# turbo_jumper.net
KiCad netlist of a schematic drawn in EAGLE
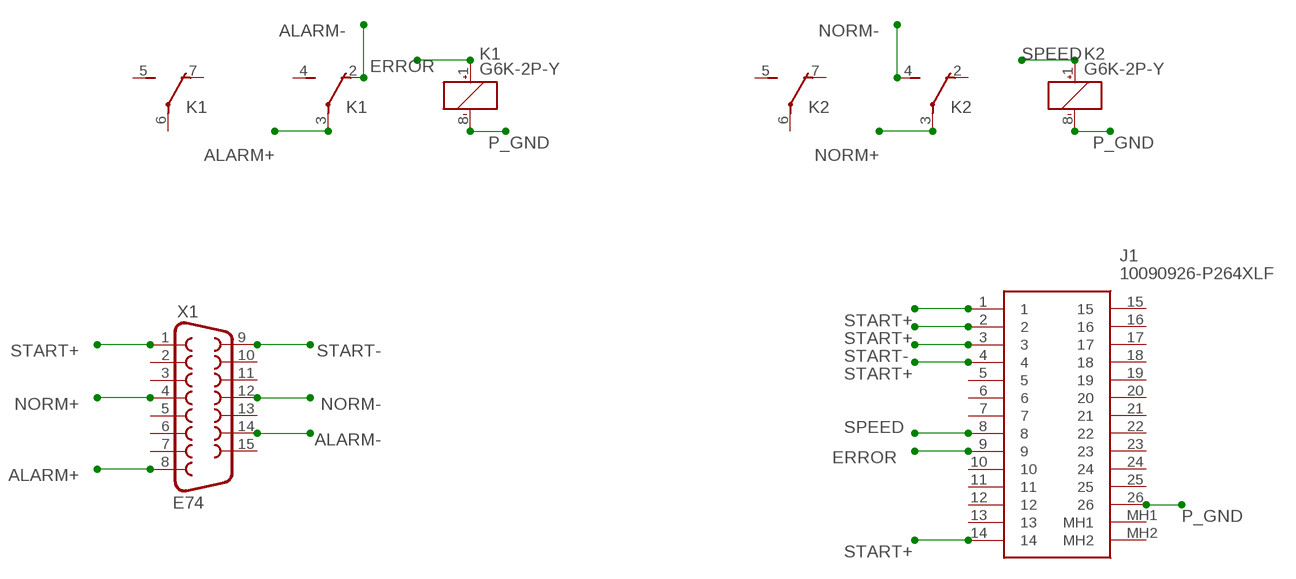
[diagram p0: schematic, sheet 1]

(export (version "E")
  (design (tool "Eeschema 10.0.6"))
  (components
    (comp (ref "J1")
      (value "10090926-P264XLF")
      (footprint "eagle-import:10090926P264XLF")
      (fields (field (name "MOUSER_PART_NUMBER") "649-10090926-P264XLF"))
      (libsource (lib "eagle-import") (part "10090926-P264XLF"))
    )
    (comp (ref "K1")
      (value "G6K-2P-Y")
      (footprint "eagle-import:G6K-2P-Y")
      (fields (field (name "MF") "OMRON COMPONENTS USA") (field (name "MPN") "G6K-2P-Y DC12"))
      (libsource (lib "eagle-import") (part "G6K-2P-Y"))
    )
    (comp (ref "K2")
      (value "G6K-2P-Y")
      (footprint "eagle-import:G6K-2P-Y")
      (fields (field (name "MF") "OMRON COMPONENTS USA") (field (name "MPN") "G6K-2P-Y DC12"))
      (libsource (lib "eagle-import") (part "G6K-2P-Y"))
    )
    (comp (ref "X1")
      (value "E74")
      (footprint "eagle-import:F15VP")
      (libsource (lib "eagle-import") (part "F15VP"))
    )
  )
  (nets
    (net (code "1") (name "/ALARM+") (class "Default")
      (node (ref "K1") (pin "3") (pinfunction "P_3") (pintype "passive"))
      (node (ref "X1") (pin "8") (pinfunction "8_8") (pintype "passive"))
    )
    (net (code "2") (name "/ALARM-") (class "Default")
      (node (ref "K1") (pin "2") (pinfunction "O_2") (pintype "passive"))
      (node (ref "X1") (pin "14") (pinfunction "14_14") (pintype "passive"))
    )
    (net (code "3") (name "/ERROR") (class "Default")
      (node (ref "J1") (pin "9") (pinfunction "9_9") (pintype "bidirectional"))
      (node (ref "K1") (pin "1") (pinfunction "+_1") (pintype "passive"))
    )
    (net (code "4") (name "/NORM+") (class "Default")
      (node (ref "K2") (pin "3") (pinfunction "P_3") (pintype "passive"))
      (node (ref "X1") (pin "4") (pinfunction "4_4") (pintype "passive"))
    )
    (net (code "5") (name "/NORM-") (class "Default")
      (node (ref "K2") (pin "4") (pinfunction "S_4") (pintype "passive"))
      (node (ref "X1") (pin "12") (pinfunction "12_12") (pintype "passive"))
    )
    (net (code "6") (name "/P_GND") (class "Default")
      (node (ref "J1") (pin "26") (pinfunction "26_26") (pintype "bidirectional"))
      (node (ref "K1") (pin "8") (pinfunction "-_8") (pintype "passive"))
      (node (ref "K2") (pin "8") (pinfunction "-_8") (pintype "passive"))
    )
    (net (code "7") (name "/SPEED") (class "Default")
      (node (ref "J1") (pin "8") (pinfunction "8_8") (pintype "bidirectional"))
      (node (ref "K2") (pin "1") (pinfunction "+_1") (pintype "passive"))
    )
    (net (code "8") (name "/START+") (class "Default")
      (node (ref "J1") (pin "1") (pinfunction "1_1") (pintype "bidirectional"))
      (node (ref "J1") (pin "14") (pinfunction "14_14") (pintype "bidirectional"))
      (node (ref "J1") (pin "2") (pinfunction "2_2") (pintype "bidirectional"))
      (node (ref "J1") (pin "4") (pinfunction "4_4") (pintype "bidirectional"))
      (node (ref "X1") (pin "1") (pinfunction "1_1") (pintype "passive"))
    )
    (net (code "9") (name "/START-") (class "Default")
      (node (ref "J1") (pin "3") (pinfunction "3_3") (pintype "bidirectional"))
      (node (ref "X1") (pin "9") (pinfunction "9_9") (pintype "passive"))
    )
    (net (code "10") (name "unconnected-(J1-Pad5)") (class "Default")
      (node (ref "J1") (pin "5") (pinfunction "5_5") (pintype "bidirectional"))
    )
    (net (code "11") (name "unconnected-(J1-Pad6)") (class "Default")
      (node (ref "J1") (pin "6") (pinfunction "6_6") (pintype "bidirectional"))
    )
    (net (code "12") (name "unconnected-(J1-Pad7)") (class "Default")
      (node (ref "J1") (pin "7") (pinfunction "7_7") (pintype "bidirectional"))
    )
    (net (code "13") (name "unconnected-(J1-Pad10)") (class "Default")
      (node (ref "J1") (pin "10") (pinfunction "10_10") (pintype "bidirectional"))
    )
    (net (code "14") (name "unconnected-(J1-Pad11)") (class "Default")
      (node (ref "J1") (pin "11") (pinfunction "11_11") (pintype "bidirectional"))
    )
    (net (code "15") (name "unconnected-(J1-Pad12)") (class "Default")
      (node (ref "J1") (pin "12") (pinfunction "12_12") (pintype "bidirectional"))
    )
    (net (code "16") (name "unconnected-(J1-Pad13)") (class "Default")
      (node (ref "J1") (pin "13") (pinfunction "13_13") (pintype "bidirectional"))
    )
    (net (code "17") (name "unconnected-(J1-Pad15)") (class "Default")
      (node (ref "J1") (pin "15") (pinfunction "15_15") (pintype "bidirectional"))
    )
    (net (code "18") (name "unconnected-(J1-Pad16)") (class "Default")
      (node (ref "J1") (pin "16") (pinfunction "16_16") (pintype "bidirectional"))
    )
    (net (code "19") (name "unconnected-(J1-Pad17)") (class "Default")
      (node (ref "J1") (pin "17") (pinfunction "17_17") (pintype "bidirectional"))
    )
    (net (code "20") (name "unconnected-(J1-Pad18)") (class "Default")
      (node (ref "J1") (pin "18") (pinfunction "18_18") (pintype "bidirectional"))
    )
    (net (code "21") (name "unconnected-(J1-Pad19)") (class "Default")
      (node (ref "J1") (pin "19") (pinfunction "19_19") (pintype "bidirectional"))
    )
    (net (code "22") (name "unconnected-(J1-Pad20)") (class "Default")
      (node (ref "J1") (pin "20") (pinfunction "20_20") (pintype "bidirectional"))
    )
    (net (code "23") (name "unconnected-(J1-Pad21)") (class "Default")
      (node (ref "J1") (pin "21") (pinfunction "21_21") (pintype "bidirectional"))
    )
    (net (code "24") (name "unconnected-(J1-Pad22)") (class "Default")
      (node (ref "J1") (pin "22") (pinfunction "22_22") (pintype "bidirectional"))
    )
    (net (code "25") (name "unconnected-(J1-Pad23)") (class "Default")
      (node (ref "J1") (pin "23") (pinfunction "23_23") (pintype "bidirectional"))
    )
    (net (code "26") (name "unconnected-(J1-Pad24)") (class "Default")
      (node (ref "J1") (pin "24") (pinfunction "24_24") (pintype "bidirectional"))
    )
    (net (code "27") (name "unconnected-(J1-Pad25)") (class "Default")
      (node (ref "J1") (pin "25") (pinfunction "25_25") (pintype "bidirectional"))
    )
    (net (code "28") (name "unconnected-(J1-PadMH1)") (class "Default")
      (node (ref "J1") (pin "MH1") (pinfunction "MH1_MH1") (pintype "bidirectional"))
    )
    (net (code "29") (name "unconnected-(J1-PadMH2)") (class "Default")
      (node (ref "J1") (pin "MH2") (pinfunction "MH2_MH2") (pintype "bidirectional"))
    )
    (net (code "30") (name "unconnected-(K1B-S-Pad4)") (class "Default")
      (node (ref "K1") (pin "4") (pinfunction "S_4") (pintype "passive"))
    )
    (net (code "31") (name "unconnected-(K1C-O-Pad7)") (class "Default")
      (node (ref "K1") (pin "7") (pinfunction "O_7") (pintype "passive"))
    )
    (net (code "32") (name "unconnected-(K1C-P-Pad6)") (class "Default")
      (node (ref "K1") (pin "6") (pinfunction "P_6") (pintype "passive"))
    )
    (net (code "33") (name "unconnected-(K1C-S-Pad5)") (class "Default")
      (node (ref "K1") (pin "5") (pinfunction "S_5") (pintype "passive"))
    )
    (net (code "34") (name "unconnected-(K2B-O-Pad2)") (class "Default")
      (node (ref "K2") (pin "2") (pinfunction "O_2") (pintype "passive"))
    )
    (net (code "35") (name "unconnected-(K2C-O-Pad7)") (class "Default")
      (node (ref "K2") (pin "7") (pinfunction "O_7") (pintype "passive"))
    )
    (net (code "36") (name "unconnected-(K2C-P-Pad6)") (class "Default")
      (node (ref "K2") (pin "6") (pinfunction "P_6") (pintype "passive"))
    )
    (net (code "37") (name "unconnected-(K2C-S-Pad5)") (class "Default")
      (node (ref "K2") (pin "5") (pinfunction "S_5") (pintype "passive"))
    )
    (net (code "38") (name "unconnected-(X1-Pad2)") (class "Default")
      (node (ref "X1") (pin "2") (pinfunction "2_2") (pintype "passive"))
    )
    (net (code "39") (name "unconnected-(X1-Pad3)") (class "Default")
      (node (ref "X1") (pin "3") (pinfunction "3_3") (pintype "passive"))
    )
    (net (code "40") (name "unconnected-(X1-Pad5)") (class "Default")
      (node (ref "X1") (pin "5") (pinfunction "5_5") (pintype "passive"))
    )
    (net (code "41") (name "unconnected-(X1-Pad6)") (class "Default")
      (node (ref "X1") (pin "6") (pinfunction "6_6") (pintype "passive"))
    )
    (net (code "42") (name "unconnected-(X1-Pad7)") (class "Default")
      (node (ref "X1") (pin "7") (pinfunction "7_7") (pintype "passive"))
    )
    (net (code "43") (name "unconnected-(X1-Pad10)") (class "Default")
      (node (ref "X1") (pin "10") (pinfunction "10_10") (pintype "passive"))
    )
    (net (code "44") (name "unconnected-(X1-Pad11)") (class "Default")
      (node (ref "X1") (pin "11") (pinfunction "11_11") (pintype "passive"))
    )
    (net (code "45") (name "unconnected-(X1-Pad13)") (class "Default")
      (node (ref "X1") (pin "13") (pinfunction "13_13") (pintype "passive"))
    )
    (net (code "46") (name "unconnected-(X1-Pad15)") (class "Default")
      (node (ref "X1") (pin "15") (pinfunction "15_15") (pintype "passive"))
    )
  )
)
